# Headers.net
KiCad netlist of a schematic drawn in Altium Designer
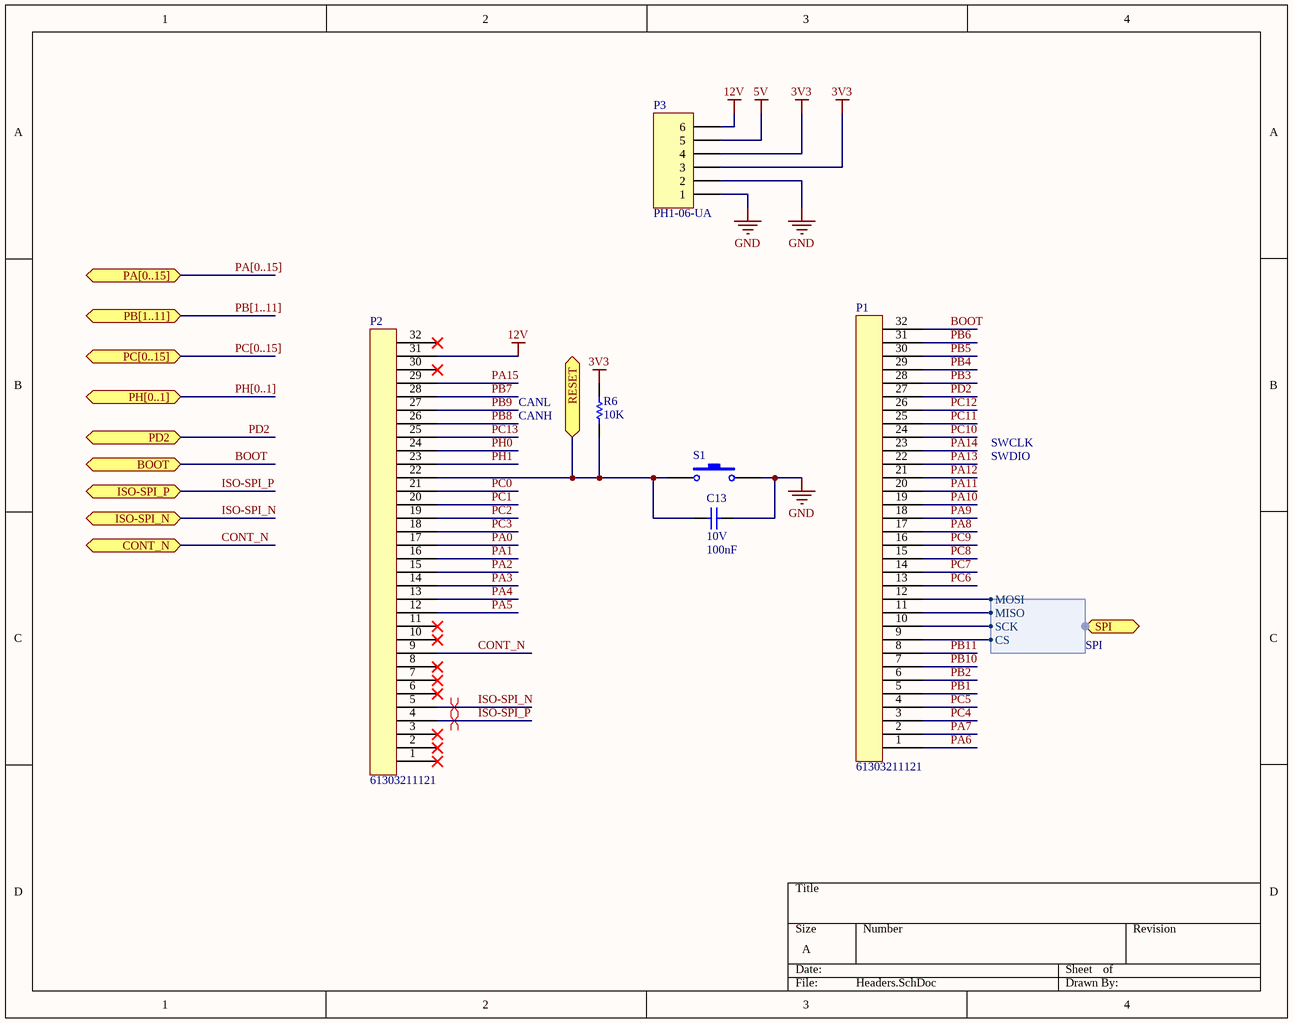
[diagram p0: Headers.SchDoc]

(export (version "E")
  (design (tool "Eeschema 10.0.6"))
  (components
    (comp (ref "C13")
      (value "10V")
      (footprint "C0805")
      (description "C0805C104K8RACTU. 0.1µF ±10% 10V Ceramic Capacitor X7R 0805 (2012 Metric)")
      (fields (field (name "ALTIUM_VALUE") "100nF") (field (name "PUBLISHER") "Altium Limited"))
      (libsource (lib "Miscellaneous Devices") (part "Cap"))
    )
    (comp (ref "P1")
      (value "61303211121")
      (footprint "61303211121")
      (libsource (lib "MCU") (part "61303211121"))
    )
    (comp (ref "P2")
      (value "61303211121")
      (footprint "61303211121")
      (libsource (lib "MCU") (part "61303211121"))
    )
    (comp (ref "P3")
      (value "PH1-06-UA")
      (footprint "PH1-06-UA")
      (description "Connector Header Through Hole 6 position 0.100\" (2.54mm)")
      (fields (field (name "PUBLISHER") "Altium Limited"))
      (libsource (lib "Miscellaneous Connectors") (part "Header 6"))
    )
    (comp (ref "R6")
      (value "10K")
      (footprint "J1-0603")
      (fields (field (name "Comment") "5%") (field (name "PUBLISHER") "Altium Limited"))
      (libsource (lib "Miscellaneous Devices") (part "Res1"))
    )
    (comp (ref "S1")
      (value "PTS636 SM43 SMTR LFS")
      (footprint "PTS636 SM43 SMTR LFS")
      (description "Tactile Switch SPST-NO Top Actuated Surface Mount")
      (fields (field (name "PUBLISHER") "Altium Limited"))
      (libsource (lib "Miscellaneous Devices") (part "SW-PB"))
    )
  )
  (nets
    (net (code "4") (name "/BOOT") (class "Default") (node (ref "P1") (pin "32") (pintype "passive")))
    (net (code "5") (name "/CONT_N") (class "Default") (node (ref "P2") (pin "9") (pintype "passive")))
    (net (code "6") (name "/CS") (class "Default") (node (ref "P1") (pin "9") (pintype "passive")))
    (net (code "7") (name "/ISO-SPI_N") (class "Default") (node (ref "P2") (pin "5") (pintype "passive")))
    (net (code "8") (name "/ISO-SPI_P") (class "Default") (node (ref "P2") (pin "4") (pintype "passive")))
    (net (code "9") (name "/MISO") (class "Default") (node (ref "P1") (pin "11") (pintype "passive")))
    (net (code "10") (name "/MOSI") (class "Default") (node (ref "P1") (pin "12") (pintype "passive")))
    (net (code "11") (name "/PA0") (class "Default") (node (ref "P2") (pin "17") (pintype "passive")))
    (net (code "12") (name "/PA1") (class "Default") (node (ref "P2") (pin "16") (pintype "passive")))
    (net (code "13") (name "/PA2") (class "Default") (node (ref "P2") (pin "15") (pintype "passive")))
    (net (code "14") (name "/PA3") (class "Default") (node (ref "P2") (pin "14") (pintype "passive")))
    (net (code "15") (name "/PA4") (class "Default") (node (ref "P2") (pin "13") (pintype "passive")))
    (net (code "16") (name "/PA5") (class "Default") (node (ref "P2") (pin "12") (pintype "passive")))
    (net (code "17") (name "/PA6") (class "Default") (node (ref "P1") (pin "1") (pintype "passive")))
    (net (code "18") (name "/PA7") (class "Default") (node (ref "P1") (pin "2") (pintype "passive")))
    (net (code "19") (name "/PA8") (class "Default") (node (ref "P1") (pin "17") (pintype "passive")))
    (net (code "20") (name "/PA9") (class "Default") (node (ref "P1") (pin "18") (pintype "passive")))
    (net (code "21") (name "/PA10") (class "Default") (node (ref "P1") (pin "19") (pintype "passive")))
    (net (code "22") (name "/PA11") (class "Default") (node (ref "P1") (pin "20") (pintype "passive")))
    (net (code "23") (name "/PA12") (class "Default") (node (ref "P1") (pin "21") (pintype "passive")))
    (net (code "24") (name "/PA13") (class "Default") (node (ref "P1") (pin "22") (pintype "passive")))
    (net (code "25") (name "/PA14") (class "Default") (node (ref "P1") (pin "23") (pintype "passive")))
    (net (code "26") (name "/PA15") (class "Default") (node (ref "P2") (pin "29") (pintype "passive")))
    (net (code "28") (name "/PB1") (class "Default") (node (ref "P1") (pin "5") (pintype "passive")))
    (net (code "29") (name "/PB2") (class "Default") (node (ref "P1") (pin "6") (pintype "passive")))
    (net (code "30") (name "/PB3") (class "Default") (node (ref "P1") (pin "28") (pintype "passive")))
    (net (code "31") (name "/PB4") (class "Default") (node (ref "P1") (pin "29") (pintype "passive")))
    (net (code "32") (name "/PB5") (class "Default") (node (ref "P1") (pin "30") (pintype "passive")))
    (net (code "33") (name "/PB6") (class "Default") (node (ref "P1") (pin "31") (pintype "passive")))
    (net (code "34") (name "/PB7") (class "Default") (node (ref "P2") (pin "28") (pintype "passive")))
    (net (code "35") (name "/PB8") (class "Default") (node (ref "P2") (pin "26") (pintype "passive")))
    (net (code "36") (name "/PB9") (class "Default") (node (ref "P2") (pin "27") (pintype "passive")))
    (net (code "37") (name "/PB10") (class "Default") (node (ref "P1") (pin "7") (pintype "passive")))
    (net (code "38") (name "/PB11") (class "Default") (node (ref "P1") (pin "8") (pintype "passive")))
    (net (code "40") (name "/PC0") (class "Default") (node (ref "P2") (pin "21") (pintype "passive")))
    (net (code "41") (name "/PC1") (class "Default") (node (ref "P2") (pin "20") (pintype "passive")))
    (net (code "42") (name "/PC2") (class "Default") (node (ref "P2") (pin "19") (pintype "passive")))
    (net (code "43") (name "/PC3") (class "Default") (node (ref "P2") (pin "18") (pintype "passive")))
    (net (code "44") (name "/PC4") (class "Default") (node (ref "P1") (pin "3") (pintype "passive")))
    (net (code "45") (name "/PC5") (class "Default") (node (ref "P1") (pin "4") (pintype "passive")))
    (net (code "46") (name "/PC6") (class "Default") (node (ref "P1") (pin "13") (pintype "passive")))
    (net (code "47") (name "/PC7") (class "Default") (node (ref "P1") (pin "14") (pintype "passive")))
    (net (code "48") (name "/PC8") (class "Default") (node (ref "P1") (pin "15") (pintype "passive")))
    (net (code "49") (name "/PC9") (class "Default") (node (ref "P1") (pin "16") (pintype "passive")))
    (net (code "50") (name "/PC10") (class "Default") (node (ref "P1") (pin "24") (pintype "passive")))
    (net (code "51") (name "/PC11") (class "Default") (node (ref "P1") (pin "25") (pintype "passive")))
    (net (code "52") (name "/PC12") (class "Default") (node (ref "P1") (pin "26") (pintype "passive")))
    (net (code "53") (name "/PC13") (class "Default") (node (ref "P2") (pin "25") (pintype "passive")))
    (net (code "55") (name "/PD2") (class "Default") (node (ref "P1") (pin "27") (pintype "passive")))
    (net (code "56") (name "/PH0") (class "Default") (node (ref "P2") (pin "24") (pintype "passive")))
    (net (code "57") (name "/PH1") (class "Default") (node (ref "P2") (pin "23") (pintype "passive")))
    (net (code "59") (name "/RESET") (class "Default")
      (node (ref "C13") (pin "1") (pinfunction "1_1") (pintype "passive"))
      (node (ref "P2") (pin "22") (pintype "passive"))
      (node (ref "R6") (pin "1") (pinfunction "1_1") (pintype "passive"))
      (node (ref "S1") (pin "1") (pinfunction "1_1") (pintype "passive"))
    )
    (net (code "60") (name "/SCK") (class "Default") (node (ref "P1") (pin "10") (pintype "passive")))
    (net (code "62") (name "3V3") (class "Default")
      (node (ref "P3") (pin "3") (pinfunction "3_3") (pintype "passive"))
      (node (ref "P3") (pin "4") (pinfunction "4_4") (pintype "passive"))
      (node (ref "R6") (pin "2") (pinfunction "2_2") (pintype "passive"))
    )
    (net (code "63") (name "5V") (class "Default")
      (node (ref "P3") (pin "5") (pinfunction "5_5") (pintype "passive"))
    )
    (net (code "64") (name "12V") (class "Default")
      (node (ref "P2") (pin "31") (pintype "passive"))
      (node (ref "P3") (pin "6") (pinfunction "6_6") (pintype "passive"))
    )
    (net (code "65") (name "GND") (class "Default")
      (node (ref "C13") (pin "2") (pinfunction "2_2") (pintype "passive"))
      (node (ref "P3") (pin "1") (pinfunction "1_1") (pintype "passive"))
      (node (ref "P3") (pin "2") (pinfunction "2_2") (pintype "passive"))
      (node (ref "S1") (pin "2") (pinfunction "2_2") (pintype "passive"))
    )
    (net (code "66") (name "unconnected-(P2-Pad1)") (class "Default")
      (node (ref "P2") (pin "1") (pintype "passive+no_connect"))
    )
    (net (code "67") (name "unconnected-(P2-Pad2)") (class "Default")
      (node (ref "P2") (pin "2") (pintype "passive+no_connect"))
    )
    (net (code "68") (name "unconnected-(P2-Pad3)") (class "Default")
      (node (ref "P2") (pin "3") (pintype "passive+no_connect"))
    )
    (net (code "69") (name "unconnected-(P2-Pad6)") (class "Default")
      (node (ref "P2") (pin "6") (pintype "passive+no_connect"))
    )
    (net (code "70") (name "unconnected-(P2-Pad7)") (class "Default")
      (node (ref "P2") (pin "7") (pintype "passive+no_connect"))
    )
    (net (code "71") (name "unconnected-(P2-Pad8)") (class "Default")
      (node (ref "P2") (pin "8") (pintype "passive+no_connect"))
    )
    (net (code "72") (name "unconnected-(P2-Pad10)") (class "Default")
      (node (ref "P2") (pin "10") (pintype "passive+no_connect"))
    )
    (net (code "73") (name "unconnected-(P2-Pad11)") (class "Default")
      (node (ref "P2") (pin "11") (pintype "passive+no_connect"))
    )
    (net (code "74") (name "unconnected-(P2-Pad30)") (class "Default")
      (node (ref "P2") (pin "30") (pintype "passive+no_connect"))
    )
    (net (code "75") (name "unconnected-(P2-Pad32)") (class "Default")
      (node (ref "P2") (pin "32") (pintype "passive+no_connect"))
    )
  )
)
